# Controller_Board_Interface.net
KiCad netlist of a schematic drawn in Altium Designer
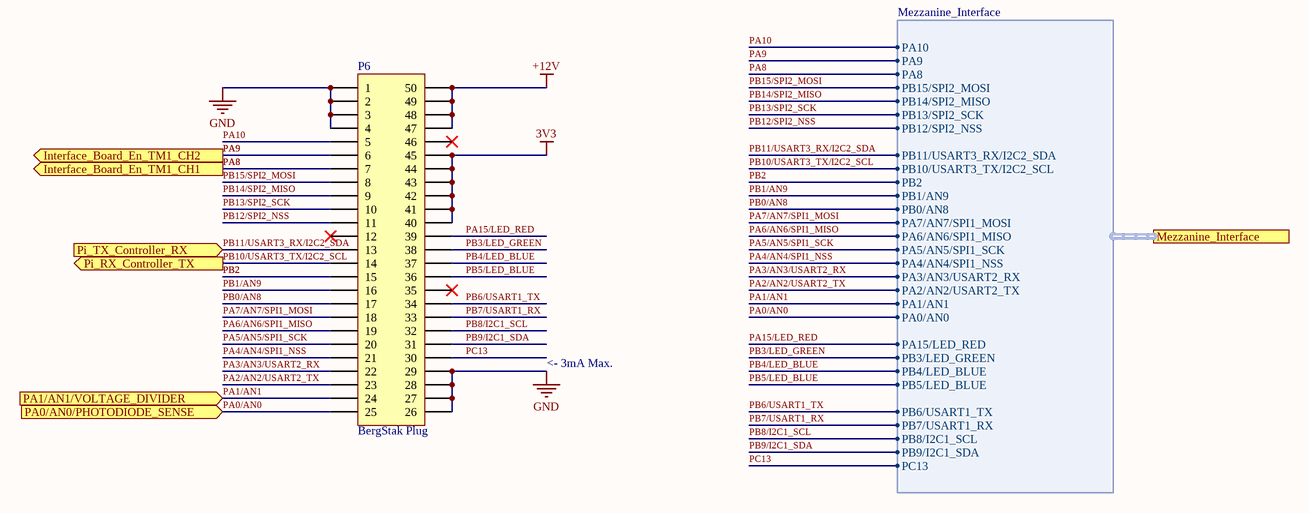
[diagram p0: Controller_Board_Interface.SchDoc]

(export (version "E")
  (design (tool "Eeschema 10.0.6"))
  (components
    (comp (ref "P6")
      (value "CONN 50POS Bergstak Plug 0.02\"")
      (footprint "CONN, Bergstak 50 Pos Plug")
      (description "50 Position Connector Plug, Outer Shroud Contacts Surface Mount Gold")
      (fields (field (name "SERIES") "BergStak Plug"))
      (libsource (lib "Schematic Diagrams") (part "CONN 50POS Bergstak Plug 0.02{dblquote}"))
    )
  )
  (nets
    (net (code "2") (name "+12V") (class "Default")
      (node (ref "P6") (pin "47") (pinfunction "47_47") (pintype "passive"))
      (node (ref "P6") (pin "48") (pinfunction "48_48") (pintype "passive"))
      (node (ref "P6") (pin "49") (pinfunction "49_49") (pintype "passive"))
      (node (ref "P6") (pin "50") (pinfunction "50_50") (pintype "passive"))
    )
    (net (code "3") (name "/PA0{slash}AN0") (class "Default")
      (node (ref "P6") (pin "25") (pinfunction "25_25") (pintype "passive"))
    )
    (net (code "4") (name "/PA1{slash}AN1") (class "Default")
      (node (ref "P6") (pin "24") (pinfunction "24_24") (pintype "passive"))
    )
    (net (code "5") (name "/PA2{slash}AN2{slash}USART2_TX") (class "Default")
      (node (ref "P6") (pin "23") (pinfunction "23_23") (pintype "passive"))
    )
    (net (code "6") (name "/PA3{slash}AN3{slash}USART2_RX") (class "Default")
      (node (ref "P6") (pin "22") (pinfunction "22_22") (pintype "passive"))
    )
    (net (code "7") (name "/PA4{slash}AN4{slash}SPI1_NSS") (class "Default")
      (node (ref "P6") (pin "21") (pinfunction "21_21") (pintype "passive"))
    )
    (net (code "8") (name "/PA5{slash}AN5{slash}SPI1_SCK") (class "Default")
      (node (ref "P6") (pin "20") (pinfunction "20_20") (pintype "passive"))
    )
    (net (code "9") (name "/PA6{slash}AN6{slash}SPI1_MISO") (class "Default")
      (node (ref "P6") (pin "19") (pinfunction "19_19") (pintype "passive"))
    )
    (net (code "10") (name "/PA7{slash}AN7{slash}SPI1_MOSI") (class "Default")
      (node (ref "P6") (pin "18") (pinfunction "18_18") (pintype "passive"))
    )
    (net (code "11") (name "/PA8") (class "Default")
      (node (ref "P6") (pin "7") (pinfunction "7_7") (pintype "passive"))
    )
    (net (code "12") (name "/PA9") (class "Default")
      (node (ref "P6") (pin "6") (pinfunction "6_6") (pintype "passive"))
    )
    (net (code "13") (name "/PA10") (class "Default")
      (node (ref "P6") (pin "5") (pinfunction "5_5") (pintype "passive"))
    )
    (net (code "14") (name "/PA15{slash}LED_RED") (class "Default")
      (node (ref "P6") (pin "39") (pinfunction "39_39") (pintype "passive"))
    )
    (net (code "15") (name "/PB0{slash}AN8") (class "Default")
      (node (ref "P6") (pin "17") (pinfunction "17_17") (pintype "passive"))
    )
    (net (code "16") (name "/PB1{slash}AN9") (class "Default")
      (node (ref "P6") (pin "16") (pinfunction "16_16") (pintype "passive"))
    )
    (net (code "17") (name "/PB2") (class "Default")
      (node (ref "P6") (pin "15") (pinfunction "15_15") (pintype "passive"))
    )
    (net (code "18") (name "/PB3{slash}LED_GREEN") (class "Default")
      (node (ref "P6") (pin "38") (pinfunction "38_38") (pintype "passive"))
    )
    (net (code "19") (name "/PB4{slash}LED_BLUE") (class "Default")
      (node (ref "P6") (pin "37") (pinfunction "37_37") (pintype "passive"))
    )
    (net (code "20") (name "/PB5{slash}LED_BLUE") (class "Default")
      (node (ref "P6") (pin "36") (pinfunction "36_36") (pintype "passive"))
    )
    (net (code "21") (name "/PB6{slash}USART1_TX") (class "Default")
      (node (ref "P6") (pin "34") (pinfunction "34_34") (pintype "passive"))
    )
    (net (code "22") (name "/PB7{slash}USART1_RX") (class "Default")
      (node (ref "P6") (pin "33") (pinfunction "33_33") (pintype "passive"))
    )
    (net (code "23") (name "/PB8{slash}I2C1_SCL") (class "Default")
      (node (ref "P6") (pin "32") (pinfunction "32_32") (pintype "passive"))
    )
    (net (code "24") (name "/PB9{slash}I2C1_SDA") (class "Default")
      (node (ref "P6") (pin "31") (pinfunction "31_31") (pintype "passive"))
    )
    (net (code "25") (name "/PB10{slash}USART3_TX{slash}I2C2_SCL") (class "Default")
      (node (ref "P6") (pin "14") (pinfunction "14_14") (pintype "passive"))
    )
    (net (code "26") (name "/PB11{slash}USART3_RX{slash}I2C2_SDA") (class "Default")
      (node (ref "P6") (pin "13") (pinfunction "13_13") (pintype "passive"))
    )
    (net (code "27") (name "/PB12{slash}SPI2_NSS") (class "Default")
      (node (ref "P6") (pin "11") (pinfunction "11_11") (pintype "passive"))
    )
    (net (code "28") (name "/PB13{slash}SPI2_SCK") (class "Default")
      (node (ref "P6") (pin "10") (pinfunction "10_10") (pintype "passive"))
    )
    (net (code "29") (name "/PB14{slash}SPI2_MISO") (class "Default")
      (node (ref "P6") (pin "9") (pinfunction "9_9") (pintype "passive"))
    )
    (net (code "30") (name "/PB15{slash}SPI2_MOSI") (class "Default")
      (node (ref "P6") (pin "8") (pinfunction "8_8") (pintype "passive"))
    )
    (net (code "31") (name "/PC13") (class "Default")
      (node (ref "P6") (pin "30") (pinfunction "30_30") (pintype "passive"))
    )
    (net (code "33") (name "3V3") (class "Default")
      (node (ref "P6") (pin "40") (pinfunction "40_40") (pintype "passive"))
      (node (ref "P6") (pin "41") (pinfunction "41_41") (pintype "passive"))
      (node (ref "P6") (pin "42") (pinfunction "42_42") (pintype "passive"))
      (node (ref "P6") (pin "43") (pinfunction "43_43") (pintype "passive"))
      (node (ref "P6") (pin "44") (pinfunction "44_44") (pintype "passive"))
      (node (ref "P6") (pin "45") (pinfunction "45_45") (pintype "passive"))
    )
    (net (code "34") (name "GND") (class "Default")
      (node (ref "P6") (pin "1") (pinfunction "1_1") (pintype "passive"))
      (node (ref "P6") (pin "2") (pinfunction "2_2") (pintype "passive"))
      (node (ref "P6") (pin "26") (pinfunction "26_26") (pintype "passive"))
      (node (ref "P6") (pin "27") (pinfunction "27_27") (pintype "passive"))
      (node (ref "P6") (pin "28") (pinfunction "28_28") (pintype "passive"))
      (node (ref "P6") (pin "29") (pinfunction "29_29") (pintype "passive"))
      (node (ref "P6") (pin "3") (pinfunction "3_3") (pintype "passive"))
      (node (ref "P6") (pin "4") (pinfunction "4_4") (pintype "passive"))
    )
    (net (code "35") (name "unconnected-(P6-Pad12)") (class "Default")
      (node (ref "P6") (pin "12") (pinfunction "12_12") (pintype "passive+no_connect"))
    )
    (net (code "36") (name "unconnected-(P6-Pad35)") (class "Default")
      (node (ref "P6") (pin "35") (pinfunction "35_35") (pintype "passive+no_connect"))
    )
    (net (code "37") (name "unconnected-(P6-Pad46)") (class "Default")
      (node (ref "P6") (pin "46") (pinfunction "46_46") (pintype "passive+no_connect"))
    )
  )
)
